# Universal_Board_Side_Mount.net
KiCad netlist of a schematic drawn in EAGLE
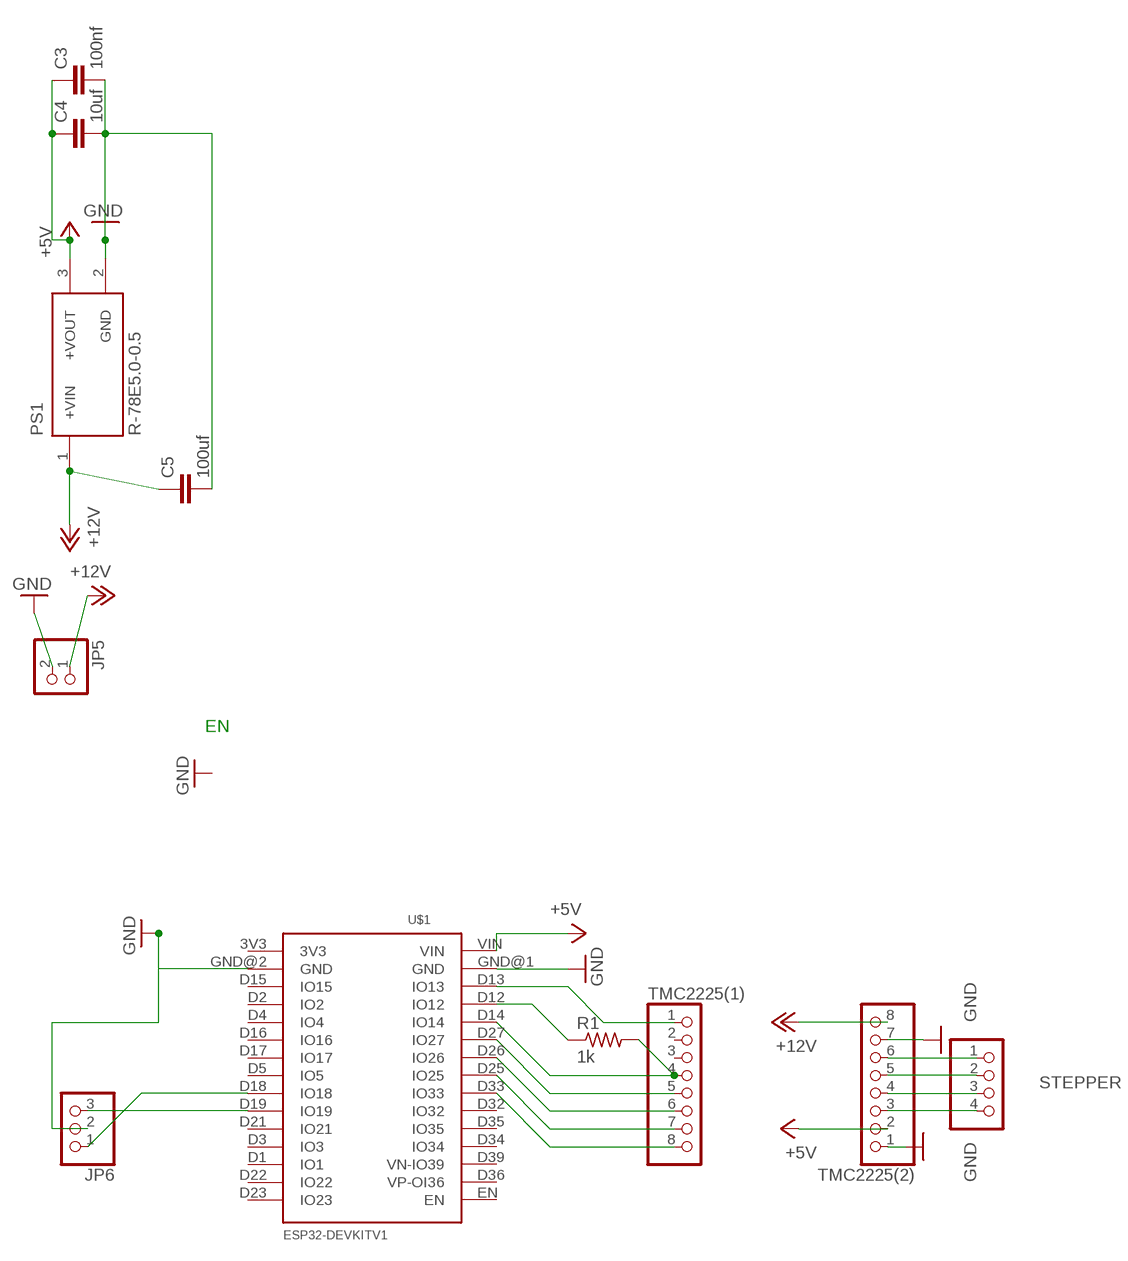
[diagram p0: schematic, sheet 1]

(export (version "E")
  (design (tool "Eeschema 10.0.6"))
  (components
    (comp (ref "C3")
      (value "100nf")
      (footprint "eagle-import:C2.5-3")
      (libsource (lib "eagle-import") (part "C2,5-3"))
    )
    (comp (ref "C4")
      (value "10uf")
      (footprint "eagle-import:C2.5-3")
      (libsource (lib "eagle-import") (part "C2,5-3"))
    )
    (comp (ref "C5")
      (value "100uf")
      (footprint "eagle-import:C2.5-3")
      (libsource (lib "eagle-import") (part "C2,5-3"))
    )
    (comp (ref "JP5")
      (value "PINHD-1X2")
      (footprint "eagle-import:1X02")
      (libsource (lib "eagle-import") (part "PINHD-1X2"))
    )
    (comp (ref "JP6")
      (value "PINHD-1X3")
      (footprint "eagle-import:1X03")
      (libsource (lib "eagle-import") (part "PINHD-1X3"))
    )
    (comp (ref "PS1")
      (value "R-78E5.0-0.5")
      (footprint "eagle-import:CONV_R-78E5.0-0.5")
      (fields (field (name "DIGI-KEY_PART_NUMBER") "945-1648-5-ND") (field (name "MF") "Recom Power"))
      (libsource (lib "eagle-import") (part "R-78E5.0-0.5"))
    )
    (comp (ref "R1")
      (value "1k")
      (footprint "eagle-import:0204_7")
      (libsource (lib "eagle-import") (part "R-US_0204/7"))
    )
    (comp (ref "STEPPER")
      (value "PINHD-1X4")
      (footprint "eagle-import:1X04")
      (libsource (lib "eagle-import") (part "PINHD-1X4"))
    )
    (comp (ref "TMC2225(1)")
      (value "PINHD-1X8")
      (footprint "eagle-import:1X08")
      (libsource (lib "eagle-import") (part "PINHD-1X8"))
    )
    (comp (ref "TMC2225(2)")
      (value "PINHD-1X8")
      (footprint "eagle-import:1X08")
      (libsource (lib "eagle-import") (part "PINHD-1X8"))
    )
    (comp (ref "U$1")
      (value "ESP32DEVKITV1")
      (footprint "eagle-import:ESP32-DEVKITV1")
      (libsource (lib "eagle-import") (part "ESP32DEVKITV1"))
    )
  )
  (nets
    (net (code "1") (name "+5V") (class "Default")
      (node (ref "C3") (pin "1") (pinfunction "1_1") (pintype "passive"))
      (node (ref "C4") (pin "1") (pinfunction "1_1") (pintype "passive"))
      (node (ref "PS1") (pin "3") (pinfunction "+VOUT_3") (pintype "output"))
      (node (ref "TMC2225(2)") (pin "2") (pinfunction "2_2") (pintype "passive"))
      (node (ref "U$1") (pin "VIN") (pinfunction "VIN_VIN") (pintype "bidirectional"))
    )
    (net (code "2") (name "+12V") (class "Default")
      (node (ref "C5") (pin "1") (pinfunction "1_1") (pintype "passive"))
      (node (ref "JP5") (pin "1") (pinfunction "1_1") (pintype "passive"))
      (node (ref "PS1") (pin "1") (pinfunction "+VIN_1") (pintype "input"))
      (node (ref "TMC2225(2)") (pin "8") (pinfunction "8_8") (pintype "passive"))
    )
    (net (code "3") (name "GND") (class "Default")
      (node (ref "C3") (pin "2") (pinfunction "2_2") (pintype "passive"))
      (node (ref "C4") (pin "2") (pinfunction "2_2") (pintype "passive"))
      (node (ref "C5") (pin "2") (pinfunction "2_2") (pintype "passive"))
      (node (ref "JP5") (pin "2") (pinfunction "2_2") (pintype "passive"))
      (node (ref "JP6") (pin "2") (pinfunction "2_2") (pintype "passive"))
      (node (ref "PS1") (pin "2") (pinfunction "GND_2") (pintype "power_in"))
      (node (ref "TMC2225(2)") (pin "1") (pinfunction "1_1") (pintype "passive"))
      (node (ref "TMC2225(2)") (pin "7") (pinfunction "7_7") (pintype "passive"))
      (node (ref "U$1") (pin "GND@1") (pinfunction "GND_GND@1") (pintype "bidirectional"))
      (node (ref "U$1") (pin "GND@2") (pinfunction "GND_GND@2") (pintype "bidirectional"))
    )
    (net (code "4") (name "Net-(STEPPER-Pad1)") (class "Default")
      (node (ref "STEPPER") (pin "1") (pinfunction "1_1") (pintype "passive"))
      (node (ref "TMC2225(2)") (pin "6") (pinfunction "6_6") (pintype "passive"))
    )
    (net (code "5") (name "Net-(STEPPER-Pad2)") (class "Default")
      (node (ref "STEPPER") (pin "2") (pinfunction "2_2") (pintype "passive"))
      (node (ref "TMC2225(2)") (pin "5") (pinfunction "5_5") (pintype "passive"))
    )
    (net (code "6") (name "Net-(STEPPER-Pad3)") (class "Default")
      (node (ref "STEPPER") (pin "3") (pinfunction "3_3") (pintype "passive"))
      (node (ref "TMC2225(2)") (pin "4") (pinfunction "4_4") (pintype "passive"))
    )
    (net (code "7") (name "Net-(STEPPER-Pad4)") (class "Default")
      (node (ref "STEPPER") (pin "4") (pinfunction "4_4") (pintype "passive"))
      (node (ref "TMC2225(2)") (pin "3") (pinfunction "3_3") (pintype "passive"))
    )
    (net (code "8") (name "Net-(U$1-IO12)") (class "Default")
      (node (ref "R1") (pin "1") (pinfunction "1_1") (pintype "passive"))
      (node (ref "U$1") (pin "D12") (pinfunction "IO12_D12") (pintype "bidirectional"))
    )
    (net (code "9") (name "Net-(U$1-IO13)") (class "Default")
      (node (ref "TMC2225(1)") (pin "1") (pinfunction "1_1") (pintype "passive"))
      (node (ref "U$1") (pin "D13") (pinfunction "IO13_D13") (pintype "bidirectional"))
    )
    (net (code "10") (name "Net-(U$1-IO14)") (class "Default")
      (node (ref "R1") (pin "2") (pinfunction "2_2") (pintype "passive"))
      (node (ref "TMC2225(1)") (pin "4") (pinfunction "4_4") (pintype "passive"))
      (node (ref "U$1") (pin "D14") (pinfunction "IO14_D14") (pintype "bidirectional"))
    )
    (net (code "11") (name "Net-(U$1-IO18)") (class "Default")
      (node (ref "JP6") (pin "1") (pinfunction "1_1") (pintype "passive"))
      (node (ref "U$1") (pin "D18") (pinfunction "IO18_D18") (pintype "bidirectional"))
    )
    (net (code "12") (name "Net-(U$1-IO19)") (class "Default")
      (node (ref "JP6") (pin "3") (pinfunction "3_3") (pintype "passive"))
      (node (ref "U$1") (pin "D19") (pinfunction "IO19_D19") (pintype "bidirectional"))
    )
    (net (code "13") (name "Net-(U$1-IO25)") (class "Default")
      (node (ref "TMC2225(1)") (pin "7") (pinfunction "7_7") (pintype "passive"))
      (node (ref "U$1") (pin "D25") (pinfunction "IO25_D25") (pintype "bidirectional"))
    )
    (net (code "14") (name "Net-(U$1-IO26)") (class "Default")
      (node (ref "TMC2225(1)") (pin "6") (pinfunction "6_6") (pintype "passive"))
      (node (ref "U$1") (pin "D26") (pinfunction "IO26_D26") (pintype "bidirectional"))
    )
    (net (code "15") (name "Net-(U$1-IO27)") (class "Default")
      (node (ref "TMC2225(1)") (pin "5") (pinfunction "5_5") (pintype "passive"))
      (node (ref "U$1") (pin "D27") (pinfunction "IO27_D27") (pintype "bidirectional"))
    )
    (net (code "16") (name "Net-(U$1-IO33)") (class "Default")
      (node (ref "TMC2225(1)") (pin "8") (pinfunction "8_8") (pintype "passive"))
      (node (ref "U$1") (pin "D33") (pinfunction "IO33_D33") (pintype "bidirectional"))
    )
    (net (code "17") (name "unconnected-(TMC2225(1)-Pad2)") (class "Default")
      (node (ref "TMC2225(1)") (pin "2") (pinfunction "2_2") (pintype "passive"))
    )
    (net (code "18") (name "unconnected-(TMC2225(1)-Pad3)") (class "Default")
      (node (ref "TMC2225(1)") (pin "3") (pinfunction "3_3") (pintype "passive"))
    )
    (net (code "19") (name "unconnected-(U$1-IO1-PadD1)") (class "Default")
      (node (ref "U$1") (pin "D1") (pinfunction "IO1_D1") (pintype "bidirectional"))
    )
    (net (code "20") (name "unconnected-(U$1-IO2-PadD2)") (class "Default")
      (node (ref "U$1") (pin "D2") (pinfunction "IO2_D2") (pintype "bidirectional"))
    )
    (net (code "21") (name "unconnected-(U$1-IO3-PadD3)") (class "Default")
      (node (ref "U$1") (pin "D3") (pinfunction "IO3_D3") (pintype "bidirectional"))
    )
    (net (code "22") (name "unconnected-(U$1-IO4-PadD4)") (class "Default")
      (node (ref "U$1") (pin "D4") (pinfunction "IO4_D4") (pintype "bidirectional"))
    )
    (net (code "23") (name "unconnected-(U$1-IO5-PadD5)") (class "Default")
      (node (ref "U$1") (pin "D5") (pinfunction "IO5_D5") (pintype "bidirectional"))
    )
    (net (code "24") (name "unconnected-(U$1-IO15-PadD15)") (class "Default")
      (node (ref "U$1") (pin "D15") (pinfunction "IO15_D15") (pintype "bidirectional"))
    )
    (net (code "25") (name "unconnected-(U$1-IO16-PadD16)") (class "Default")
      (node (ref "U$1") (pin "D16") (pinfunction "IO16_D16") (pintype "bidirectional"))
    )
    (net (code "26") (name "unconnected-(U$1-IO17-PadD17)") (class "Default")
      (node (ref "U$1") (pin "D17") (pinfunction "IO17_D17") (pintype "bidirectional"))
    )
    (net (code "27") (name "unconnected-(U$1-IO21-PadD21)") (class "Default")
      (node (ref "U$1") (pin "D21") (pinfunction "IO21_D21") (pintype "bidirectional"))
    )
    (net (code "28") (name "unconnected-(U$1-IO22-PadD22)") (class "Default")
      (node (ref "U$1") (pin "D22") (pinfunction "IO22_D22") (pintype "bidirectional"))
    )
    (net (code "29") (name "unconnected-(U$1-IO23-PadD23)") (class "Default")
      (node (ref "U$1") (pin "D23") (pinfunction "IO23_D23") (pintype "bidirectional"))
    )
    (net (code "30") (name "unconnected-(U$1-IO32-PadD32)") (class "Default")
      (node (ref "U$1") (pin "D32") (pinfunction "IO32_D32") (pintype "bidirectional"))
    )
    (net (code "31") (name "unconnected-(U$1-IO34-PadD34)") (class "Default")
      (node (ref "U$1") (pin "D34") (pinfunction "IO34_D34") (pintype "bidirectional"))
    )
    (net (code "32") (name "unconnected-(U$1-IO35-PadD35)") (class "Default")
      (node (ref "U$1") (pin "D35") (pinfunction "IO35_D35") (pintype "bidirectional"))
    )
    (net (code "33") (name "unconnected-(U$1-Pad3V3)") (class "Default")
      (node (ref "U$1") (pin "3V3") (pinfunction "3V3_3V3") (pintype "bidirectional"))
    )
    (net (code "34") (name "unconnected-(U$1-PadEN)") (class "Default")
      (node (ref "U$1") (pin "EN") (pinfunction "EN_EN") (pintype "bidirectional"))
    )
    (net (code "35") (name "unconnected-(U$1-VN-IO39-PadD39)") (class "Default")
      (node (ref "U$1") (pin "D39") (pinfunction "VN-IO39_D39") (pintype "bidirectional"))
    )
    (net (code "36") (name "unconnected-(U$1-VP-OI36-PadD36)") (class "Default")
      (node (ref "U$1") (pin "D36") (pinfunction "VP-OI36_D36") (pintype "bidirectional"))
    )
  )
)
